# v03b_1.net
KiCad netlist of a schematic drawn in EAGLE
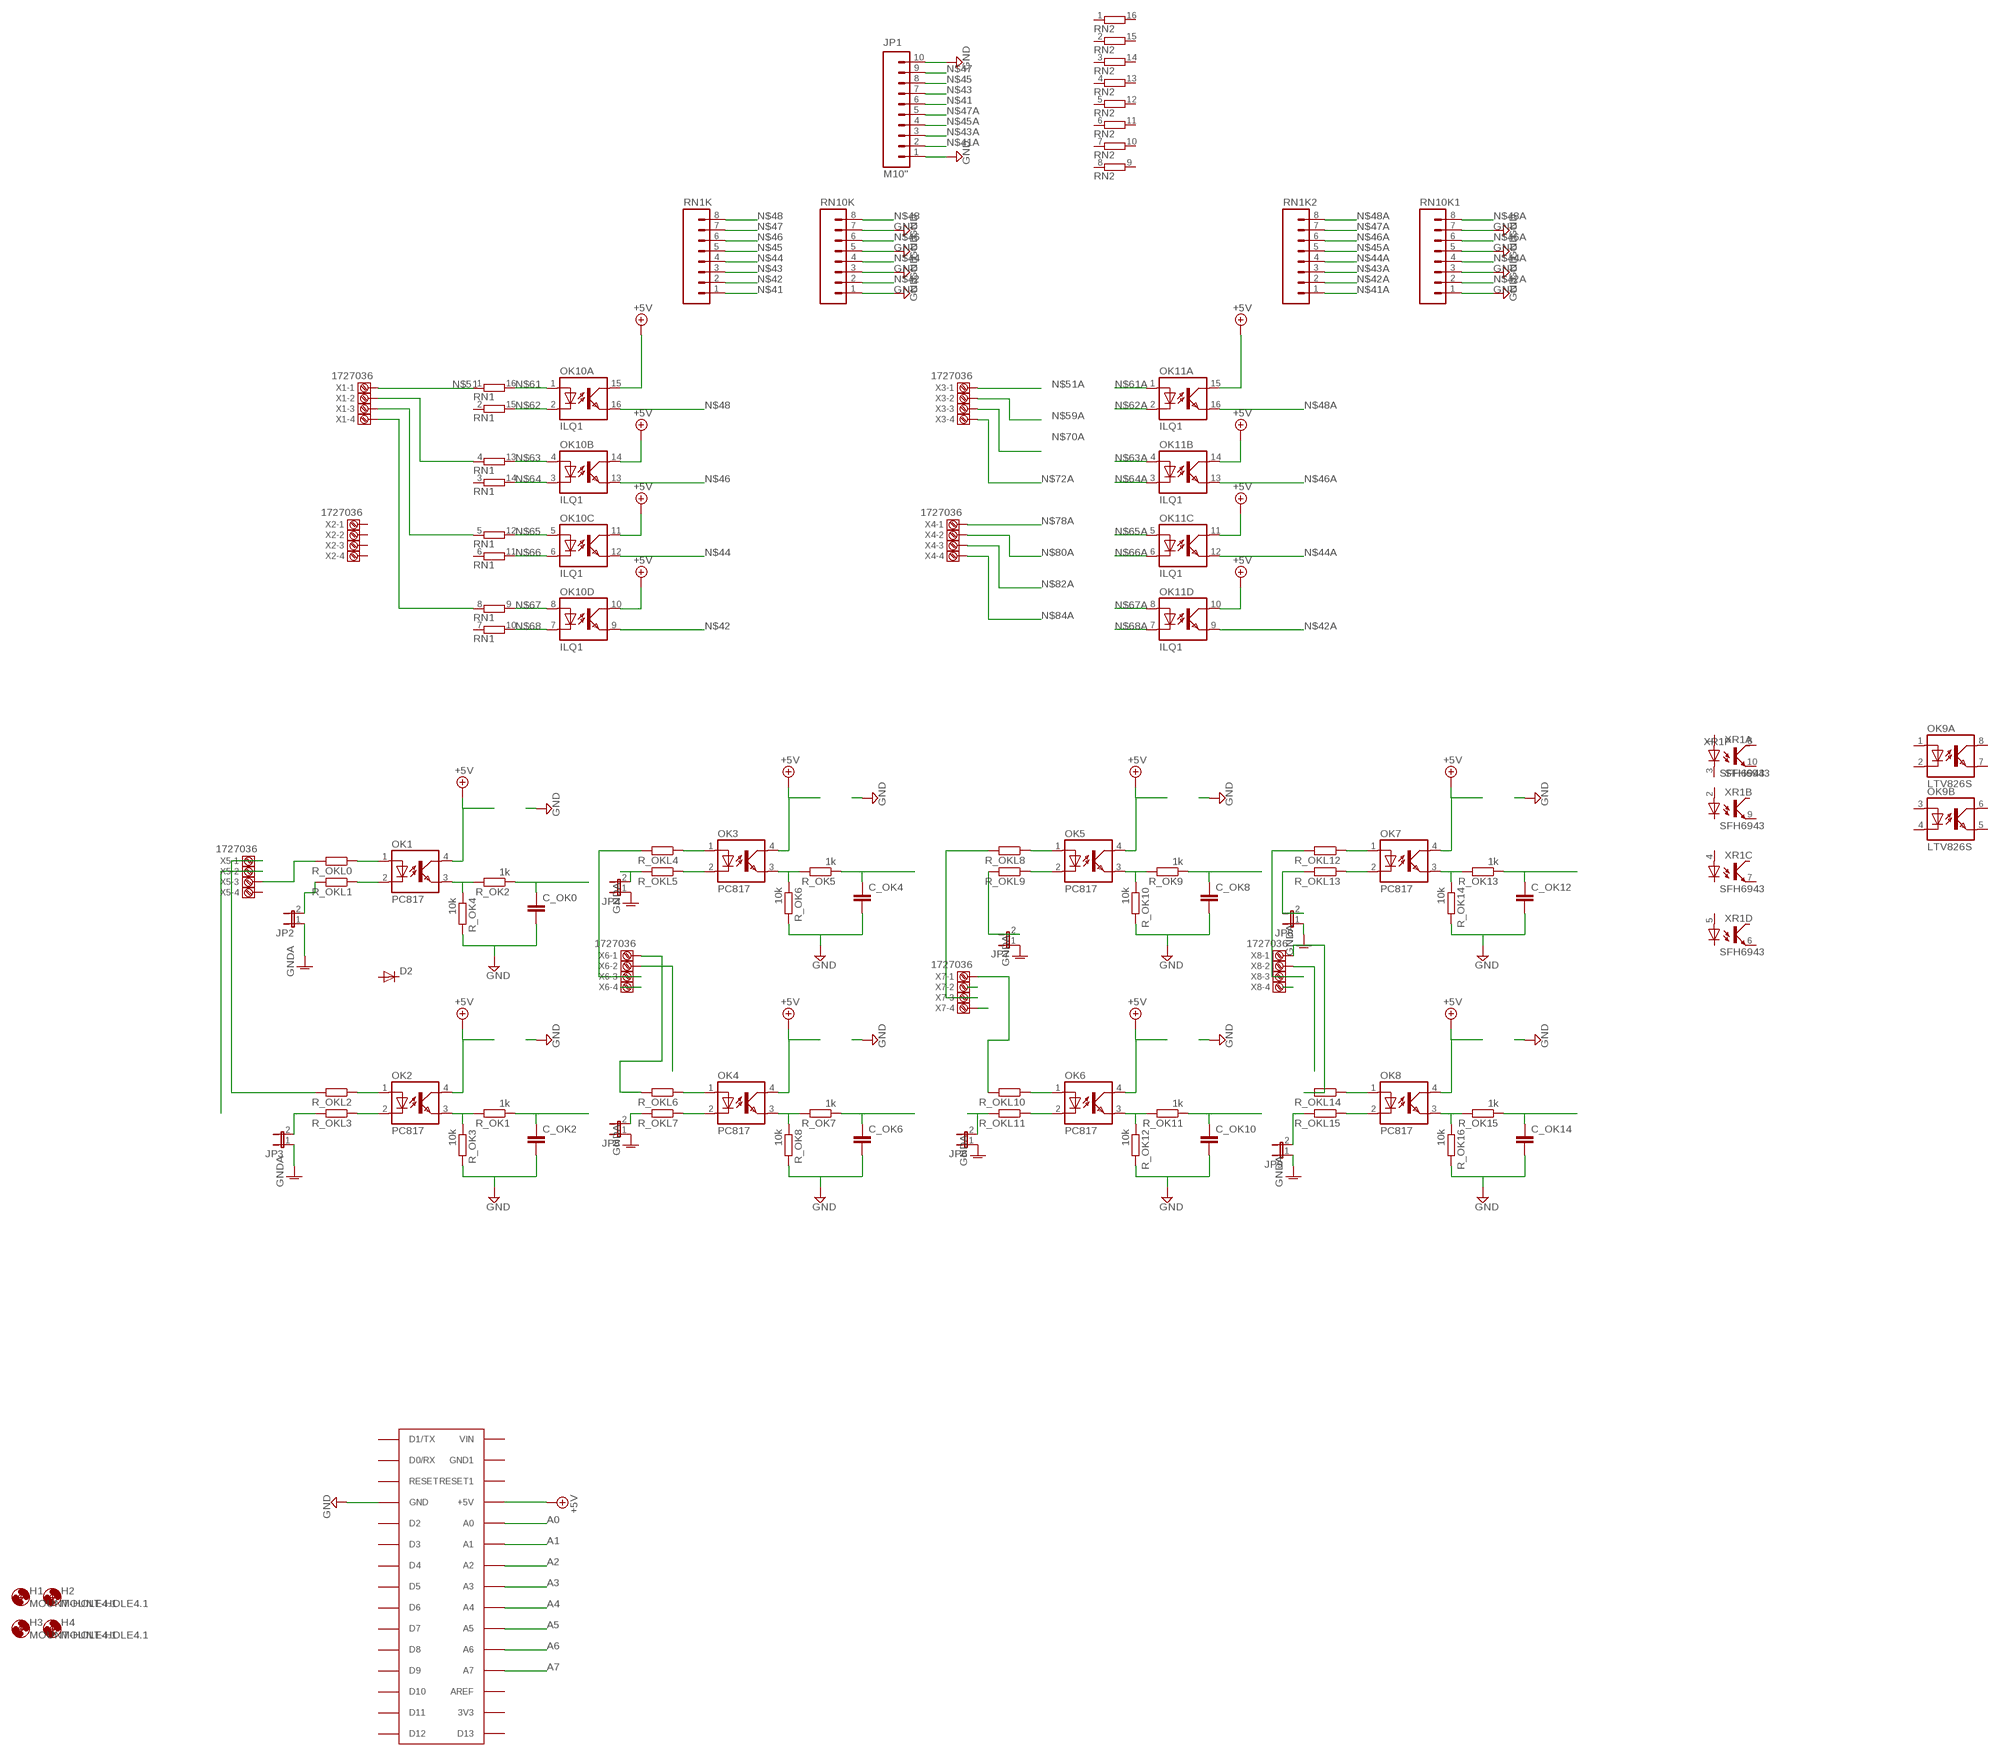
[diagram p0: schematic, sheet 1]

(export (version "E")
  (design (tool "Eeschema 10.0.6"))
  (components
    (comp (ref "C_OK0")
      (value "C-EUC0805")
      (footprint "eagle-import:C0805")
      (libsource (lib "eagle-import") (part "C-EUC0805"))
    )
    (comp (ref "C_OK2")
      (value "C-EUC0805")
      (footprint "eagle-import:C0805")
      (libsource (lib "eagle-import") (part "C-EUC0805"))
    )
    (comp (ref "C_OK4")
      (value "C-EUC0805")
      (footprint "eagle-import:C0805")
      (libsource (lib "eagle-import") (part "C-EUC0805"))
    )
    (comp (ref "C_OK6")
      (value "C-EUC0805")
      (footprint "eagle-import:C0805")
      (libsource (lib "eagle-import") (part "C-EUC0805"))
    )
    (comp (ref "C_OK8")
      (value "C-EUC0805")
      (footprint "eagle-import:C0805")
      (libsource (lib "eagle-import") (part "C-EUC0805"))
    )
    (comp (ref "C_OK10")
      (value "C-EUC0805")
      (footprint "eagle-import:C0805")
      (libsource (lib "eagle-import") (part "C-EUC0805"))
    )
    (comp (ref "C_OK12")
      (value "C-EUC0805")
      (footprint "eagle-import:C0805")
      (libsource (lib "eagle-import") (part "C-EUC0805"))
    )
    (comp (ref "C_OK14")
      (value "C-EUC0805")
      (footprint "eagle-import:C0805")
      (libsource (lib "eagle-import") (part "C-EUC0805"))
    )
    (comp (ref "D2")
      (value "DIODESOD")
      (footprint "eagle-import:SOD-323")
      (libsource (lib "eagle-import") (part "DIODESOD"))
    )
    (comp (ref "H1")
      (value "MOUNT-HOLE4.1")
      (footprint "eagle-import:4,1")
      (libsource (lib "eagle-import") (part "MOUNT-HOLE4.1"))
    )
    (comp (ref "H2")
      (value "MOUNT-HOLE4.1")
      (footprint "eagle-import:4,1")
      (libsource (lib "eagle-import") (part "MOUNT-HOLE4.1"))
    )
    (comp (ref "H3")
      (value "MOUNT-HOLE4.1")
      (footprint "eagle-import:4,1")
      (libsource (lib "eagle-import") (part "MOUNT-HOLE4.1"))
    )
    (comp (ref "H4")
      (value "MOUNT-HOLE4.1")
      (footprint "eagle-import:4,1")
      (libsource (lib "eagle-import") (part "MOUNT-HOLE4.1"))
    )
    (comp (ref "JP1")
      (value "M10\"")
      (footprint "eagle-import:1X10")
      (libsource (lib "eagle-import") (part "M10{dblquote}"))
    )
    (comp (ref "JP2")
      (value "JUMPER-2PTH")
      (footprint "eagle-import:1X02")
      (libsource (lib "eagle-import") (part "JUMPER-2PTH"))
    )
    (comp (ref "JP3")
      (value "JUMPER-2PTH")
      (footprint "eagle-import:1X02")
      (libsource (lib "eagle-import") (part "JUMPER-2PTH"))
    )
    (comp (ref "JP4")
      (value "JUMPER-2PTH")
      (footprint "eagle-import:1X02")
      (libsource (lib "eagle-import") (part "JUMPER-2PTH"))
    )
    (comp (ref "JP5")
      (value "JUMPER-2PTH")
      (footprint "eagle-import:1X02")
      (libsource (lib "eagle-import") (part "JUMPER-2PTH"))
    )
    (comp (ref "JP6")
      (value "JUMPER-2PTH")
      (footprint "eagle-import:1X02")
      (libsource (lib "eagle-import") (part "JUMPER-2PTH"))
    )
    (comp (ref "JP7")
      (value "JUMPER-2PTH")
      (footprint "eagle-import:1X02")
      (libsource (lib "eagle-import") (part "JUMPER-2PTH"))
    )
    (comp (ref "JP8")
      (value "JUMPER-2PTH")
      (footprint "eagle-import:1X02")
      (libsource (lib "eagle-import") (part "JUMPER-2PTH"))
    )
    (comp (ref "JP9")
      (value "JUMPER-2PTH")
      (footprint "eagle-import:1X02")
      (libsource (lib "eagle-import") (part "JUMPER-2PTH"))
    )
    (comp (ref "OK1")
      (value "PC817")
      (footprint "eagle-import:DIL04")
      (fields (field (name "MPN") "PC817X4J000F"))
      (libsource (lib "eagle-import") (part "PC817"))
    )
    (comp (ref "OK2")
      (value "PC817")
      (footprint "eagle-import:DIL04")
      (fields (field (name "MPN") "PC817X4J000F"))
      (libsource (lib "eagle-import") (part "PC817"))
    )
    (comp (ref "OK3")
      (value "PC817")
      (footprint "eagle-import:DIL04")
      (fields (field (name "MPN") "PC817X4J000F"))
      (libsource (lib "eagle-import") (part "PC817"))
    )
    (comp (ref "OK4")
      (value "PC817")
      (footprint "eagle-import:DIL04")
      (fields (field (name "MPN") "PC817X4J000F"))
      (libsource (lib "eagle-import") (part "PC817"))
    )
    (comp (ref "OK5")
      (value "PC817")
      (footprint "eagle-import:DIL04")
      (fields (field (name "MPN") "PC817X4J000F"))
      (libsource (lib "eagle-import") (part "PC817"))
    )
    (comp (ref "OK6")
      (value "PC817")
      (footprint "eagle-import:DIL04")
      (fields (field (name "MPN") "PC817X4J000F"))
      (libsource (lib "eagle-import") (part "PC817"))
    )
    (comp (ref "OK7")
      (value "PC817")
      (footprint "eagle-import:DIL04")
      (fields (field (name "MPN") "PC817X4J000F"))
      (libsource (lib "eagle-import") (part "PC817"))
    )
    (comp (ref "OK8")
      (value "PC817")
      (footprint "eagle-import:DIL04")
      (fields (field (name "MPN") "PC817X4J000F"))
      (libsource (lib "eagle-import") (part "PC817"))
    )
    (comp (ref "OK9")
      (value "LTV826S")
      (footprint "eagle-import:DIL8-SMD")
      (libsource (lib "eagle-import") (part "LTV826S"))
    )
    (comp (ref "OK10")
      (value "ILQ1")
      (footprint "eagle-import:DIL16")
      (fields (field (name "MF") "VISHAY/TELEFUNKEN"))
      (libsource (lib "eagle-import") (part "ILQ1"))
    )
    (comp (ref "OK11")
      (value "ILQ1")
      (footprint "eagle-import:DIL16")
      (fields (field (name "MF") "VISHAY/TELEFUNKEN"))
      (libsource (lib "eagle-import") (part "ILQ1"))
    )
    (comp (ref "RN1")
      (value "8R-PSOMC")
      (footprint "eagle-import:SOMC16")
      (libsource (lib "eagle-import") (part "8R-PSOMC"))
    )
    (comp (ref "RN1K")
      (value "M081X08")
      (footprint "eagle-import:1X08")
      (libsource (lib "eagle-import") (part "M081X08"))
    )
    (comp (ref "RN1K2")
      (value "M081X08")
      (footprint "eagle-import:1X08")
      (libsource (lib "eagle-import") (part "M081X08"))
    )
    (comp (ref "RN2")
      (value "8R-PSOMC")
      (footprint "eagle-import:SOMC16")
      (libsource (lib "eagle-import") (part "8R-PSOMC"))
    )
    (comp (ref "RN10K")
      (value "M081X08")
      (footprint "eagle-import:1X08")
      (libsource (lib "eagle-import") (part "M081X08"))
    )
    (comp (ref "RN10K1")
      (value "M081X08")
      (footprint "eagle-import:1X08")
      (libsource (lib "eagle-import") (part "M081X08"))
    )
    (comp (ref "R_OK1")
      (value "1k")
      (footprint "eagle-import:M0805")
      (libsource (lib "eagle-import") (part "R-EU_M0805"))
    )
    (comp (ref "R_OK2")
      (value "1k")
      (footprint "eagle-import:M0805")
      (libsource (lib "eagle-import") (part "R-EU_M0805"))
    )
    (comp (ref "R_OK3")
      (value "10k")
      (footprint "eagle-import:M0805")
      (libsource (lib "eagle-import") (part "R-EU_M0805"))
    )
    (comp (ref "R_OK4")
      (value "10k")
      (footprint "eagle-import:M0805")
      (libsource (lib "eagle-import") (part "R-EU_M0805"))
    )
    (comp (ref "R_OK5")
      (value "1k")
      (footprint "eagle-import:M0805")
      (libsource (lib "eagle-import") (part "R-EU_M0805"))
    )
    (comp (ref "R_OK6")
      (value "10k")
      (footprint "eagle-import:M0805")
      (libsource (lib "eagle-import") (part "R-EU_M0805"))
    )
    (comp (ref "R_OK7")
      (value "1k")
      (footprint "eagle-import:M0805")
      (libsource (lib "eagle-import") (part "R-EU_M0805"))
    )
    (comp (ref "R_OK8")
      (value "10k")
      (footprint "eagle-import:M0805")
      (libsource (lib "eagle-import") (part "R-EU_M0805"))
    )
    (comp (ref "R_OK9")
      (value "1k")
      (footprint "eagle-import:M0805")
      (libsource (lib "eagle-import") (part "R-EU_M0805"))
    )
    (comp (ref "R_OK10")
      (value "10k")
      (footprint "eagle-import:M0805")
      (libsource (lib "eagle-import") (part "R-EU_M0805"))
    )
    (comp (ref "R_OK11")
      (value "1k")
      (footprint "eagle-import:M0805")
      (libsource (lib "eagle-import") (part "R-EU_M0805"))
    )
    (comp (ref "R_OK12")
      (value "10k")
      (footprint "eagle-import:M0805")
      (libsource (lib "eagle-import") (part "R-EU_M0805"))
    )
    (comp (ref "R_OK13")
      (value "1k")
      (footprint "eagle-import:M0805")
      (libsource (lib "eagle-import") (part "R-EU_M0805"))
    )
    (comp (ref "R_OK14")
      (value "10k")
      (footprint "eagle-import:M0805")
      (libsource (lib "eagle-import") (part "R-EU_M0805"))
    )
    (comp (ref "R_OK15")
      (value "1k")
      (footprint "eagle-import:M0805")
      (libsource (lib "eagle-import") (part "R-EU_M0805"))
    )
    (comp (ref "R_OK16")
      (value "10k")
      (footprint "eagle-import:M0805")
      (libsource (lib "eagle-import") (part "R-EU_M0805"))
    )
    (comp (ref "R_OKL0")
      (value "R-EU_R1210")
      (footprint "eagle-import:R1210")
      (libsource (lib "eagle-import") (part "R-EU_R1210"))
    )
    (comp (ref "R_OKL1")
      (value "R-EU_R1210")
      (footprint "eagle-import:R1210")
      (libsource (lib "eagle-import") (part "R-EU_R1210"))
    )
    (comp (ref "R_OKL2")
      (value "R-EU_R1210")
      (footprint "eagle-import:R1210")
      (libsource (lib "eagle-import") (part "R-EU_R1210"))
    )
    (comp (ref "R_OKL3")
      (value "R-EU_R1210")
      (footprint "eagle-import:R1210")
      (libsource (lib "eagle-import") (part "R-EU_R1210"))
    )
    (comp (ref "R_OKL4")
      (value "R-EU_R1210")
      (footprint "eagle-import:R1210")
      (libsource (lib "eagle-import") (part "R-EU_R1210"))
    )
    (comp (ref "R_OKL5")
      (value "R-EU_R1210")
      (footprint "eagle-import:R1210")
      (libsource (lib "eagle-import") (part "R-EU_R1210"))
    )
    (comp (ref "R_OKL6")
      (value "R-EU_R1210")
      (footprint "eagle-import:R1210")
      (libsource (lib "eagle-import") (part "R-EU_R1210"))
    )
    (comp (ref "R_OKL7")
      (value "R-EU_R1210")
      (footprint "eagle-import:R1210")
      (libsource (lib "eagle-import") (part "R-EU_R1210"))
    )
    (comp (ref "R_OKL8")
      (value "R-EU_R1210")
      (footprint "eagle-import:R1210")
      (libsource (lib "eagle-import") (part "R-EU_R1210"))
    )
    (comp (ref "R_OKL9")
      (value "R-EU_R1210")
      (footprint "eagle-import:R1210")
      (libsource (lib "eagle-import") (part "R-EU_R1210"))
    )
    (comp (ref "R_OKL10")
      (value "R-EU_R1210")
      (footprint "eagle-import:R1210")
      (libsource (lib "eagle-import") (part "R-EU_R1210"))
    )
    (comp (ref "R_OKL11")
      (value "R-EU_R1210")
      (footprint "eagle-import:R1210")
      (libsource (lib "eagle-import") (part "R-EU_R1210"))
    )
    (comp (ref "R_OKL12")
      (value "R-EU_R1210")
      (footprint "eagle-import:R1210")
      (libsource (lib "eagle-import") (part "R-EU_R1210"))
    )
    (comp (ref "R_OKL13")
      (value "R-EU_R1210")
      (footprint "eagle-import:R1210")
      (libsource (lib "eagle-import") (part "R-EU_R1210"))
    )
    (comp (ref "R_OKL14")
      (value "R-EU_R1210")
      (footprint "eagle-import:R1210")
      (libsource (lib "eagle-import") (part "R-EU_R1210"))
    )
    (comp (ref "R_OKL15")
      (value "R-EU_R1210")
      (footprint "eagle-import:R1210")
      (libsource (lib "eagle-import") (part "R-EU_R1210"))
    )
    (comp (ref "U$1")
      (value "ARDUINONANO")
      (footprint "eagle-import:PDIP-32")
      (libsource (lib "eagle-import") (part "ARDUINONANO"))
    )
    (comp (ref "X1")
      (value "1727036")
      (footprint "eagle-import:1727036")
      (fields (field (name "MF") "FARNELL"))
      (libsource (lib "eagle-import") (part "1727036"))
    )
    (comp (ref "X2")
      (value "1727036")
      (footprint "eagle-import:1727036")
      (fields (field (name "MF") "FARNELL"))
      (libsource (lib "eagle-import") (part "1727036"))
    )
    (comp (ref "X3")
      (value "1727036")
      (footprint "eagle-import:1727036")
      (fields (field (name "MF") "FARNELL"))
      (libsource (lib "eagle-import") (part "1727036"))
    )
    (comp (ref "X4")
      (value "1727036")
      (footprint "eagle-import:1727036")
      (fields (field (name "MF") "FARNELL"))
      (libsource (lib "eagle-import") (part "1727036"))
    )
    (comp (ref "X5")
      (value "1727036")
      (footprint "eagle-import:1727036")
      (fields (field (name "MF") "FARNELL"))
      (libsource (lib "eagle-import") (part "1727036"))
    )
    (comp (ref "X6")
      (value "1727036")
      (footprint "eagle-import:1727036")
      (fields (field (name "MF") "FARNELL"))
      (libsource (lib "eagle-import") (part "1727036"))
    )
    (comp (ref "X7")
      (value "1727036")
      (footprint "eagle-import:1727036")
      (fields (field (name "MF") "FARNELL"))
      (libsource (lib "eagle-import") (part "1727036"))
    )
    (comp (ref "X8")
      (value "1727036")
      (footprint "eagle-import:1727036")
      (fields (field (name "MF") "FARNELL"))
      (libsource (lib "eagle-import") (part "1727036"))
    )
    (comp (ref "XR1")
      (value "SFH6943")
      (footprint "eagle-import:SOT223_10")
      (fields (field (name "MPN") "SFH6943A-4T"))
      (libsource (lib "eagle-import") (part "SFH6943"))
    )
  )
  (nets
    (net (code "1") (name "+5V") (class "Default")
      (node (ref "OK1") (pin "4") (pinfunction "COL_4") (pintype "passive"))
      (node (ref "OK10") (pin "10") (pinfunction "COL_10") (pintype "passive"))
      (node (ref "OK10") (pin "11") (pinfunction "COL_11") (pintype "passive"))
      (node (ref "OK10") (pin "14") (pinfunction "COL_14") (pintype "passive"))
      (node (ref "OK10") (pin "15") (pinfunction "COL_15") (pintype "passive"))
      (node (ref "OK11") (pin "10") (pinfunction "COL_10") (pintype "passive"))
      (node (ref "OK11") (pin "11") (pinfunction "COL_11") (pintype "passive"))
      (node (ref "OK11") (pin "14") (pinfunction "COL_14") (pintype "passive"))
      (node (ref "OK11") (pin "15") (pinfunction "COL_15") (pintype "passive"))
      (node (ref "OK2") (pin "4") (pinfunction "COL_4") (pintype "passive"))
      (node (ref "OK3") (pin "4") (pinfunction "COL_4") (pintype "passive"))
      (node (ref "OK4") (pin "4") (pinfunction "COL_4") (pintype "passive"))
      (node (ref "OK5") (pin "4") (pinfunction "COL_4") (pintype "passive"))
      (node (ref "OK6") (pin "4") (pinfunction "COL_4") (pintype "passive"))
      (node (ref "OK7") (pin "4") (pinfunction "COL_4") (pintype "passive"))
      (node (ref "OK8") (pin "4") (pinfunction "COL_4") (pintype "passive"))
      (node (ref "U$1") (pin "+5V") (pinfunction "+5V_+5V") (pintype "bidirectional"))
    )
    (net (code "2") (name "/A0") (class "Default")
      (node (ref "C_OK0") (pin "1") (pinfunction "1_1") (pintype "passive"))
      (node (ref "R_OK2") (pin "1") (pinfunction "1_1") (pintype "passive"))
      (node (ref "U$1") (pin "A0") (pinfunction "A0_A0") (pintype "bidirectional"))
    )
    (net (code "3") (name "/A1") (class "Default")
      (node (ref "C_OK2") (pin "1") (pinfunction "1_1") (pintype "passive"))
      (node (ref "R_OK1") (pin "1") (pinfunction "1_1") (pintype "passive"))
      (node (ref "U$1") (pin "A1") (pinfunction "A1_A1") (pintype "bidirectional"))
    )
    (net (code "4") (name "/A2") (class "Default")
      (node (ref "C_OK4") (pin "1") (pinfunction "1_1") (pintype "passive"))
      (node (ref "R_OK5") (pin "1") (pinfunction "1_1") (pintype "passive"))
      (node (ref "U$1") (pin "A2") (pinfunction "A2_A2") (pintype "bidirectional"))
    )
    (net (code "5") (name "/A3") (class "Default")
      (node (ref "C_OK6") (pin "1") (pinfunction "1_1") (pintype "passive"))
      (node (ref "R_OK7") (pin "1") (pinfunction "1_1") (pintype "passive"))
      (node (ref "U$1") (pin "A3") (pinfunction "A3_A3") (pintype "bidirectional"))
    )
    (net (code "6") (name "/A4") (class "Default")
      (node (ref "C_OK8") (pin "1") (pinfunction "1_1") (pintype "passive"))
      (node (ref "R_OK9") (pin "1") (pinfunction "1_1") (pintype "passive"))
      (node (ref "U$1") (pin "A4") (pinfunction "A4_A4") (pintype "bidirectional"))
    )
    (net (code "7") (name "/A5") (class "Default")
      (node (ref "C_OK10") (pin "1") (pinfunction "1_1") (pintype "passive"))
      (node (ref "R_OK11") (pin "1") (pinfunction "1_1") (pintype "passive"))
      (node (ref "U$1") (pin "A5") (pinfunction "A5_A5") (pintype "bidirectional"))
    )
    (net (code "8") (name "/A6") (class "Default")
      (node (ref "C_OK12") (pin "1") (pinfunction "1_1") (pintype "passive"))
      (node (ref "R_OK13") (pin "1") (pinfunction "1_1") (pintype "passive"))
      (node (ref "U$1") (pin "A6") (pinfunction "A6_A6") (pintype "bidirectional"))
    )
    (net (code "9") (name "/A7") (class "Default")
      (node (ref "C_OK14") (pin "1") (pinfunction "1_1") (pintype "passive"))
      (node (ref "R_OK15") (pin "1") (pinfunction "1_1") (pintype "passive"))
      (node (ref "U$1") (pin "A7") (pinfunction "A7_A7") (pintype "bidirectional"))
    )
    (net (code "10") (name "/N$41") (class "Default")
      (node (ref "JP1") (pin "6") (pinfunction "6_6") (pintype "passive"))
      (node (ref "RN1K") (pin "1") (pinfunction "1_1") (pintype "passive"))
    )
    (net (code "11") (name "/N$41A") (class "Default")
      (node (ref "JP1") (pin "2") (pinfunction "2_2") (pintype "passive"))
      (node (ref "RN1K2") (pin "1") (pinfunction "1_1") (pintype "passive"))
    )
    (net (code "12") (name "/N$42") (class "Default")
      (node (ref "OK10") (pin "9") (pinfunction "EMIT_9") (pintype "passive"))
      (node (ref "RN10K") (pin "2") (pinfunction "2_2") (pintype "passive"))
      (node (ref "RN1K") (pin "2") (pinfunction "2_2") (pintype "passive"))
    )
    (net (code "13") (name "/N$42A") (class "Default")
      (node (ref "OK11") (pin "9") (pinfunction "EMIT_9") (pintype "passive"))
      (node (ref "RN10K1") (pin "2") (pinfunction "2_2") (pintype "passive"))
      (node (ref "RN1K2") (pin "2") (pinfunction "2_2") (pintype "passive"))
    )
    (net (code "14") (name "/N$43") (class "Default")
      (node (ref "JP1") (pin "7") (pinfunction "7_7") (pintype "passive"))
      (node (ref "RN1K") (pin "3") (pinfunction "3_3") (pintype "passive"))
    )
    (net (code "15") (name "/N$43A") (class "Default")
      (node (ref "JP1") (pin "3") (pinfunction "3_3") (pintype "passive"))
      (node (ref "RN1K2") (pin "3") (pinfunction "3_3") (pintype "passive"))
    )
    (net (code "16") (name "/N$44") (class "Default")
      (node (ref "OK10") (pin "12") (pinfunction "EMIT_12") (pintype "passive"))
      (node (ref "RN10K") (pin "4") (pinfunction "4_4") (pintype "passive"))
      (node (ref "RN1K") (pin "4") (pinfunction "4_4") (pintype "passive"))
    )
    (net (code "17") (name "/N$44A") (class "Default")
      (node (ref "OK11") (pin "12") (pinfunction "EMIT_12") (pintype "passive"))
      (node (ref "RN10K1") (pin "4") (pinfunction "4_4") (pintype "passive"))
      (node (ref "RN1K2") (pin "4") (pinfunction "4_4") (pintype "passive"))
    )
    (net (code "18") (name "/N$45") (class "Default")
      (node (ref "JP1") (pin "8") (pinfunction "8_8") (pintype "passive"))
      (node (ref "RN1K") (pin "5") (pinfunction "5_5") (pintype "passive"))
    )
    (net (code "19") (name "/N$45A") (class "Default")
      (node (ref "JP1") (pin "4") (pinfunction "4_4") (pintype "passive"))
      (node (ref "RN1K2") (pin "5") (pinfunction "5_5") (pintype "passive"))
    )
    (net (code "20") (name "/N$46") (class "Default")
      (node (ref "OK10") (pin "13") (pinfunction "EMIT_13") (pintype "passive"))
      (node (ref "RN10K") (pin "6") (pinfunction "6_6") (pintype "passive"))
      (node (ref "RN1K") (pin "6") (pinfunction "6_6") (pintype "passive"))
    )
    (net (code "21") (name "/N$46A") (class "Default")
      (node (ref "OK11") (pin "13") (pinfunction "EMIT_13") (pintype "passive"))
      (node (ref "RN10K1") (pin "6") (pinfunction "6_6") (pintype "passive"))
      (node (ref "RN1K2") (pin "6") (pinfunction "6_6") (pintype "passive"))
    )
    (net (code "22") (name "/N$47") (class "Default")
      (node (ref "JP1") (pin "9") (pinfunction "9_9") (pintype "passive"))
      (node (ref "RN1K") (pin "7") (pinfunction "7_7") (pintype "passive"))
    )
    (net (code "23") (name "/N$47A") (class "Default")
      (node (ref "JP1") (pin "5") (pinfunction "5_5") (pintype "passive"))
      (node (ref "RN1K2") (pin "7") (pinfunction "7_7") (pintype "passive"))
    )
    (net (code "24") (name "/N$48") (class "Default")
      (node (ref "OK10") (pin "16") (pinfunction "EMIT_16") (pintype "passive"))
      (node (ref "RN10K") (pin "8") (pinfunction "8_8") (pintype "passive"))
      (node (ref "RN1K") (pin "8") (pinfunction "8_8") (pintype "passive"))
    )
    (net (code "25") (name "/N$48A") (class "Default")
      (node (ref "OK11") (pin "16") (pinfunction "EMIT_16") (pintype "passive"))
      (node (ref "RN10K1") (pin "8") (pinfunction "8_8") (pintype "passive"))
      (node (ref "RN1K2") (pin "8") (pinfunction "8_8") (pintype "passive"))
    )
    (net (code "26") (name "/N$51") (class "Default")
      (node (ref "RN1") (pin "1") (pinfunction "1_1") (pintype "passive"))
      (node (ref "X1") (pin "1") (pinfunction "1_1") (pintype "passive"))
    )
    (net (code "27") (name "/N$51A") (class "Default")
      (node (ref "X3") (pin "1") (pinfunction "1_1") (pintype "passive"))
    )
    (net (code "28") (name "/N$59A") (class "Default")
      (node (ref "X3") (pin "2") (pinfunction "1_2") (pintype "passive"))
    )
    (net (code "29") (name "/N$61") (class "Default")
      (node (ref "OK10") (pin "1") (pinfunction "A_1") (pintype "passive"))
      (node (ref "RN1") (pin "16") (pinfunction "2_16") (pintype "passive"))
    )
    (net (code "30") (name "/N$61A") (class "Default")
      (node (ref "OK11") (pin "1") (pinfunction "A_1") (pintype "passive"))
    )
    (net (code "31") (name "/N$62") (class "Default")
      (node (ref "OK10") (pin "2") (pinfunction "C_2") (pintype "passive"))
      (node (ref "RN1") (pin "15") (pinfunction "2_15") (pintype "passive"))
    )
    (net (code "32") (name "/N$62A") (class "Default")
      (node (ref "OK11") (pin "2") (pinfunction "C_2") (pintype "passive"))
    )
    (net (code "33") (name "/N$63") (class "Default")
      (node (ref "OK10") (pin "4") (pinfunction "A_4") (pintype "passive"))
      (node (ref "RN1") (pin "13") (pinfunction "2_13") (pintype "passive"))
    )
    (net (code "34") (name "/N$63A") (class "Default")
      (node (ref "OK11") (pin "4") (pinfunction "A_4") (pintype "passive"))
    )
    (net (code "35") (name "/N$64") (class "Default")
      (node (ref "OK10") (pin "3") (pinfunction "C_3") (pintype "passive"))
      (node (ref "RN1") (pin "14") (pinfunction "2_14") (pintype "passive"))
    )
    (net (code "36") (name "/N$64A") (class "Default")
      (node (ref "OK11") (pin "3") (pinfunction "C_3") (pintype "passive"))
    )
    (net (code "37") (name "/N$65") (class "Default")
      (node (ref "OK10") (pin "5") (pinfunction "A_5") (pintype "passive"))
      (node (ref "RN1") (pin "12") (pinfunction "2_12") (pintype "passive"))
    )
    (net (code "38") (name "/N$65A") (class "Default")
      (node (ref "OK11") (pin "5") (pinfunction "A_5") (pintype "passive"))
    )
    (net (code "39") (name "/N$66") (class "Default")
      (node (ref "OK10") (pin "6") (pinfunction "C_6") (pintype "passive"))
      (node (ref "RN1") (pin "11") (pinfunction "2_11") (pintype "passive"))
    )
    (net (code "40") (name "/N$66A") (class "Default")
      (node (ref "OK11") (pin "6") (pinfunction "C_6") (pintype "passive"))
    )
    (net (code "41") (name "/N$67") (class "Default")
      (node (ref "OK10") (pin "8") (pinfunction "A_8") (pintype "passive"))
      (node (ref "RN1") (pin "9") (pinfunction "2_9") (pintype "passive"))
    )
    (net (code "42") (name "/N$67A") (class "Default")
      (node (ref "OK11") (pin "8") (pinfunction "A_8") (pintype "passive"))
    )
    (net (code "43") (name "/N$68") (class "Default")
      (node (ref "OK10") (pin "7") (pinfunction "C_7") (pintype "passive"))
      (node (ref "RN1") (pin "10") (pinfunction "2_10") (pintype "passive"))
    )
    (net (code "44") (name "/N$68A") (class "Default")
      (node (ref "OK11") (pin "7") (pinfunction "C_7") (pintype "passive"))
    )
    (net (code "45") (name "/N$70A") (class "Default")
      (node (ref "X3") (pin "3") (pinfunction "1_3") (pintype "passive"))
    )
    (net (code "46") (name "/N$72A") (class "Default")
      (node (ref "X3") (pin "4") (pinfunction "1_4") (pintype "passive"))
    )
    (net (code "47") (name "/N$78A") (class "Default")
      (node (ref "X4") (pin "1") (pinfunction "1_1") (pintype "passive"))
    )
    (net (code "48") (name "/N$80A") (class "Default")
      (node (ref "X4") (pin "2") (pinfunction "1_2") (pintype "passive"))
    )
    (net (code "49") (name "/N$82A") (class "Default")
      (node (ref "X4") (pin "3") (pinfunction "1_3") (pintype "passive"))
    )
    (net (code "50") (name "/N$84A") (class "Default")
      (node (ref "X4") (pin "4") (pinfunction "1_4") (pintype "passive"))
    )
    (net (code "51") (name "GND") (class "Default")
      (node (ref "C_OK0") (pin "2") (pinfunction "2_2") (pintype "passive"))
      (node (ref "C_OK10") (pin "2") (pinfunction "2_2") (pintype "passive"))
      (node (ref "C_OK12") (pin "2") (pinfunction "2_2") (pintype "passive"))
      (node (ref "C_OK14") (pin "2") (pinfunction "2_2") (pintype "passive"))
      (node (ref "C_OK2") (pin "2") (pinfunction "2_2") (pintype "passive"))
      (node (ref "C_OK4") (pin "2") (pinfunction "2_2") (pintype "passive"))
      (node (ref "C_OK6") (pin "2") (pinfunction "2_2") (pintype "passive"))
      (node (ref "C_OK8") (pin "2") (pinfunction "2_2") (pintype "passive"))
      (node (ref "JP1") (pin "1") (pinfunction "1_1") (pintype "passive"))
      (node (ref "JP1") (pin "10") (pinfunction "10_10") (pintype "passive"))
      (node (ref "RN10K") (pin "1") (pinfunction "1_1") (pintype "passive"))
      (node (ref "RN10K") (pin "3") (pinfunction "3_3") (pintype "passive"))
      (node (ref "RN10K") (pin "5") (pinfunction "5_5") (pintype "passive"))
      (node (ref "RN10K") (pin "7") (pinfunction "7_7") (pintype "passive"))
      (node (ref "RN10K1") (pin "1") (pinfunction "1_1") (pintype "passive"))
      (node (ref "RN10K1") (pin "3") (pinfunction "3_3") (pintype "passive"))
      (node (ref "RN10K1") (pin "5") (pinfunction "5_5") (pintype "passive"))
      (node (ref "RN10K1") (pin "7") (pinfunction "7_7") (pintype "passive"))
      (node (ref "R_OK10") (pin "2") (pinfunction "2_2") (pintype "passive"))
      (node (ref "R_OK12") (pin "2") (pinfunction "2_2") (pintype "passive"))
      (node (ref "R_OK14") (pin "2") (pinfunction "2_2") (pintype "passive"))
      (node (ref "R_OK16") (pin "2") (pinfunction "2_2") (pintype "passive"))
      (node (ref "R_OK3") (pin "2") (pinfunction "2_2") (pintype "passive"))
      (node (ref "R_OK4") (pin "2") (pinfunction "2_2") (pintype "passive"))
      (node (ref "R_OK6") (pin "2") (pinfunction "2_2") (pintype "passive"))
      (node (ref "R_OK8") (pin "2") (pinfunction "2_2") (pintype "passive"))
      (node (ref "U$1") (pin "GND") (pinfunction "GND_GND") (pintype "bidirectional"))
    )
    (net (code "52") (name "GNDA") (class "Default")
      (node (ref "JP2") (pin "1") (pinfunction "1_1") (pintype "passive"))
      (node (ref "JP3") (pin "1") (pinfunction "1_1") (pintype "passive"))
      (node (ref "JP4") (pin "1") (pinfunction "1_1") (pintype "passive"))
      (node (ref "JP5") (pin "1") (pinfunction "1_1") (pintype "passive"))
      (node (ref "JP6") (pin "1") (pinfunction "1_1") (pintype "passive"))
      (node (ref "JP7") (pin "1") (pinfunction "1_1") (pintype "passive"))
      (node (ref "JP8") (pin "1") (pinfunction "1_1") (pintype "passive"))
      (node (ref "JP9") (pin "1") (pinfunction "1_1") (pintype "passive"))
    )
    (net (code "53") (name "Net-(JP2-Pad2)") (class "Default")
      (node (ref "JP2") (pin "2") (pinfunction "2_2") (pintype "passive"))
      (node (ref "R_OKL1") (pin "2") (pinfunction "2_2") (pintype "passive"))
    )
    (net (code "54") (name "Net-(JP3-Pad2)") (class "Default")
      (node (ref "JP3") (pin "2") (pinfunction "2_2") (pintype "passive"))
      (node (ref "R_OKL3") (pin "2") (pinfunction "2_2") (pintype "passive"))
    )
    (net (code "55") (name "Net-(JP4-Pad2)") (class "Default")
      (node (ref "JP4") (pin "2") (pinfunction "2_2") (pintype "passive"))
      (node (ref "R_OKL5") (pin "2") (pinfunction "2_2") (pintype "passive"))
    )
    (net (code "56") (name "Net-(JP5-Pad2)") (class "Default")
      (node (ref "JP5") (pin "2") (pinfunction "2_2") (pintype "passive"))
      (node (ref "R_OKL7") (pin "2") (pinfunction "2_2") (pintype "passive"))
    )
    (net (code "57") (name "Net-(JP6-Pad2)") (class "Default")
      (node (ref "JP6") (pin "2") (pinfunction "2_2") (pintype "passive"))
      (node (ref "R_OKL11") (pin "2") (pinfunction "2_2") (pintype "passive"))
    )
    (net (code "58") (name "Net-(JP7-Pad2)") (class "Default")
      (node (ref "JP7") (pin "2") (pinfunction "2_2") (pintype "passive"))
      (node (ref "R_OKL9") (pin "2") (pinfunction "2_2") (pintype "passive"))
    )
    (net (code "59") (name "Net-(JP8-Pad2)") (class "Default")
      (node (ref "JP8") (pin "2") (pinfunction "2_2") (pintype "passive"))
      (node (ref "R_OKL13") (pin "2") (pinfunction "2_2") (pintype "passive"))
    )
    (net (code "60") (name "Net-(JP9-Pad2)") (class "Default")
      (node (ref "JP9") (pin "2") (pinfunction "2_2") (pintype "passive"))
      (node (ref "R_OKL15") (pin "2") (pinfunction "2_2") (pintype "passive"))
    )
    (net (code "61") (name "Net-(OK1-A)") (class "Default")
      (node (ref "OK1") (pin "1") (pinfunction "A_1") (pintype "passive"))
      (node (ref "R_OKL0") (pin "1") (pinfunction "1_1") (pintype "passive"))
    )
    (net (code "62") (name "Net-(OK1-C)") (class "Default")
      (node (ref "OK1") (pin "2") (pinfunction "C_2") (pintype "passive"))
      (node (ref "R_OKL1") (pin "1") (pinfunction "1_1") (pintype "passive"))
    )
    (net (code "63") (name "Net-(OK1-EMIT)") (class "Default")
      (node (ref "OK1") (pin "3") (pinfunction "EMIT_3") (pintype "passive"))
      (node (ref "R_OK2") (pin "2") (pinfunction "2_2") (pintype "passive"))
      (node (ref "R_OK4") (pin "1") (pinfunction "1_1") (pintype "passive"))
    )
    (net (code "64") (name "Net-(OK2-A)") (class "Default")
      (node (ref "OK2") (pin "1") (pinfunction "A_1") (pintype "passive"))
      (node (ref "R_OKL2") (pin "1") (pinfunction "1_1") (pintype "passive"))
    )
    (net (code "65") (name "Net-(OK2-C)") (class "Default")
      (node (ref "OK2") (pin "2") (pinfunction "C_2") (pintype "passive"))
      (node (ref "R_OKL3") (pin "1") (pinfunction "1_1") (pintype "passive"))
    )
    (net (code "66") (name "Net-(OK2-EMIT)") (class "Default")
      (node (ref "OK2") (pin "3") (pinfunction "EMIT_3") (pintype "passive"))
      (node (ref "R_OK1") (pin "2") (pinfunction "2_2") (pintype "passive"))
      (node (ref "R_OK3") (pin "1") (pinfunction "1_1") (pintype "passive"))
    )
    (net (code "67") (name "Net-(OK3-A)") (class "Default")
      (node (ref "OK3") (pin "1") (pinfunction "A_1") (pintype "passive"))
      (node (ref "R_OKL4") (pin "1") (pinfunction "1_1") (pintype "passive"))
    )
    (net (code "68") (name "Net-(OK3-C)") (class "Default")
      (node (ref "OK3") (pin "2") (pinfunction "C_2") (pintype "passive"))
      (node (ref "R_OKL5") (pin "1") (pinfunction "1_1") (pintype "passive"))
    )
    (net (code "69") (name "Net-(OK3-EMIT)") (class "Default")
      (node (ref "OK3") (pin "3") (pinfunction "EMIT_3") (pintype "passive"))
      (node (ref "R_OK5") (pin "2") (pinfunction "2_2") (pintype "passive"))
      (node (ref "R_OK6") (pin "1") (pinfunction "1_1") (pintype "passive"))
    )
    (net (code "70") (name "Net-(OK4-A)") (class "Default")
      (node (ref "OK4") (pin "1") (pinfunction "A_1") (pintype "passive"))
      (node (ref "R_OKL6") (pin "1") (pinfunction "1_1") (pintype "passive"))
    )
    (net (code "71") (name "Net-(OK4-C)") (class "Default")
      (node (ref "OK4") (pin "2") (pinfunction "C_2") (pintype "passive"))
      (node (ref "R_OKL7") (pin "1") (pinfunction "1_1") (pintype "passive"))
    )
    (net (code "72") (name "Net-(OK4-EMIT)") (class "Default")
      (node (ref "OK4") (pin "3") (pinfunction "EMIT_3") (pintype "passive"))
      (node (ref "R_OK7") (pin "2") (pinfunction "2_2") (pintype "passive"))
      (node (ref "R_OK8") (pin "1") (pinfunction "1_1") (pintype "passive"))
    )
    (net (code "73") (name "Net-(OK5-A)") (class "Default")
      (node (ref "OK5") (pin "1") (pinfunction "A_1") (pintype "passive"))
      (node (ref "R_OKL8") (pin "1") (pinfunction "1_1") (pintype "passive"))
    )
    (net (code "74") (name "Net-(OK5-C)") (class "Default")
      (node (ref "OK5") (pin "2") (pinfunction "C_2") (pintype "passive"))
      (node (ref "R_OKL9") (pin "1") (pinfunction "1_1") (pintype "passive"))
    )
    (net (code "75") (name "Net-(OK5-EMIT)") (class "Default")
      (node (ref "OK5") (pin "3") (pinfunction "EMIT_3") (pintype "passive"))
      (node (ref "R_OK10") (pin "1") (pinfunction "1_1") (pintype "passive"))
      (node (ref "R_OK9") (pin "2") (pinfunction "2_2") (pintype "passive"))
    )
    (net (code "76") (name "Net-(OK6-A)") (class "Default")
      (node (ref "OK6") (pin "1") (pinfunction "A_1") (pintype "passive"))
      (node (ref "R_OKL10") (pin "1") (pinfunction "1_1") (pintype "passive"))
    )
    (net (code "77") (name "Net-(OK6-C)") (class "Default")
      (node (ref "OK6") (pin "2") (pinfunction "C_2") (pintype "passive"))
      (node (ref "R_OKL11") (pin "1") (pinfunction "1_1") (pintype "passive"))
    )
    (net (code "78") (name "Net-(OK6-EMIT)") (class "Default")
      (node (ref "OK6") (pin "3") (pinfunction "EMIT_3") (pintype "passive"))
      (node (ref "R_OK11") (pin "2") (pinfunction "2_2") (pintype "passive"))
      (node (ref "R_OK12") (pin "1") (pinfunction "1_1") (pintype "passive"))
    )
    (net (code "79") (name "Net-(OK7-A)") (class "Default")
      (node (ref "OK7") (pin "1") (pinfunction "A_1") (pintype "passive"))
      (node (ref "R_OKL12") (pin "1") (pinfunction "1_1") (pintype "passive"))
    )
    (net (code "80") (name "Net-(OK7-C)") (class "Default")
      (node (ref "OK7") (pin "2") (pinfunction "C_2") (pintype "passive"))
      (node (ref "R_OKL13") (pin "1") (pinfunction "1_1") (pintype "passive"))
    )
    (net (code "81") (name "Net-(OK7-EMIT)") (class "Default")
      (node (ref "OK7") (pin "3") (pinfunction "EMIT_3") (pintype "passive"))
      (node (ref "R_OK13") (pin "2") (pinfunction "2_2") (pintype "passive"))
      (node (ref "R_OK14") (pin "1") (pinfunction "1_1") (pintype "passive"))
    )
    (net (code "82") (name "Net-(OK8-A)") (class "Default")
      (node (ref "OK8") (pin "1") (pinfunction "A_1") (pintype "passive"))
      (node (ref "R_OKL14") (pin "1") (pinfunction "1_1") (pintype "passive"))
    )
    (net (code "83") (name "Net-(OK8-C)") (class "Default")
      (node (ref "OK8") (pin "2") (pinfunction "C_2") (pintype "passive"))
      (node (ref "R_OKL15") (pin "1") (pinfunction "1_1") (pintype "passive"))
    )
    (net (code "84") (name "Net-(OK8-EMIT)") (class "Default")
      (node (ref "OK8") (pin "3") (pinfunction "EMIT_3") (pintype "passive"))
      (node (ref "R_OK15") (pin "2") (pinfunction "2_2") (pintype "passive"))
      (node (ref "R_OK16") (pin "1") (pinfunction "1_1") (pintype "passive"))
    )
    (net (code "85") (name "Net-(RN1D-1)") (class "Default")
      (node (ref "RN1") (pin "4") (pinfunction "1_4") (pintype "passive"))
      (node (ref "X1") (pin "2") (pinfunction "1_2") (pintype "passive"))
    )
    (net (code "86") (name "Net-(RN1E-1)") (class "Default")
      (node (ref "RN1") (pin "5") (pinfunction "1_5") (pintype "passive"))
      (node (ref "X1") (pin "3") (pinfunction "1_3") (pintype "passive"))
    )
    (net (code "87") (name "Net-(RN1H-1)") (class "Default")
      (node (ref "RN1") (pin "8") (pinfunction "1_8") (pintype "passive"))
      (node (ref "X1") (pin "4") (pinfunction "1_4") (pintype "passive"))
    )
    (net (code "88") (name "Net-(R_OKL2-Pad2)") (class "Default")
      (node (ref "R_OKL2") (pin "2") (pinfunction "2_2") (pintype "passive"))
      (node (ref "X5") (pin "1") (pinfunction "1_1") (pintype "passive"))
    )
    (net (code "89") (name "Net-(R_OKL6-Pad2)") (class "Default")
      (node (ref "R_OKL6") (pin "2") (pinfunction "2_2") (pintype "passive"))
      (node (ref "X6") (pin "1") (pinfunction "1_1") (pintype "passive"))
    )
    (net (code "90") (name "Net-(R_OKL10-Pad2)") (class "Default")
      (node (ref "R_OKL10") (pin "2") (pinfunction "2_2") (pintype "passive"))
      (node (ref "X7") (pin "1") (pinfunction "1_1") (pintype "passive"))
    )
    (net (code "91") (name "Net-(R_OKL14-Pad2)") (class "Default")
      (node (ref "R_OKL14") (pin "2") (pinfunction "2_2") (pintype "passive"))
      (node (ref "X8") (pin "1") (pinfunction "1_1") (pintype "passive"))
    )
    (net (code "92") (name "Net-(X5C-1)") (class "Default")
      (node (ref "R_OKL0") (pin "2") (pinfunction "2_2") (pintype "passive"))
      (node (ref "X5") (pin "3") (pinfunction "1_3") (pintype "passive"))
    )
    (net (code "93") (name "Net-(X6C-1)") (class "Default")
      (node (ref "R_OKL4") (pin "2") (pinfunction "2_2") (pintype "passive"))
      (node (ref "X6") (pin "3") (pinfunction "1_3") (pintype "passive"))
    )
    (net (code "94") (name "Net-(X7C-1)") (class "Default")
      (node (ref "R_OKL8") (pin "2") (pinfunction "2_2") (pintype "passive"))
      (node (ref "X7") (pin "3") (pinfunction "1_3") (pintype "passive"))
    )
    (net (code "95") (name "Net-(X8C-1)") (class "Default")
      (node (ref "R_OKL12") (pin "2") (pinfunction "2_2") (pintype "passive"))
      (node (ref "X8") (pin "3") (pinfunction "1_3") (pintype "passive"))
    )
    (net (code "96") (name "unconnected-(D2-A-Pad2)") (class "Default")
      (node (ref "D2") (pin "2") (pinfunction "A_2") (pintype "passive"))
    )
    (net (code "97") (name "unconnected-(D2-C-Pad1)") (class "Default")
      (node (ref "D2") (pin "1") (pinfunction "C_1") (pintype "passive"))
    )
    (net (code "98") (name "unconnected-(OK9A-A-Pad1)") (class "Default")
      (node (ref "OK9") (pin "1") (pinfunction "A_1") (pintype "passive"))
    )
    (net (code "99") (name "unconnected-(OK9A-C-Pad2)") (class "Default")
      (node (ref "OK9") (pin "2") (pinfunction "C_2") (pintype "passive"))
    )
    (net (code "100") (name "unconnected-(OK9A-COL-Pad8)") (class "Default")
      (node (ref "OK9") (pin "8") (pinfunction "COL_8") (pintype "passive"))
    )
    (net (code "101") (name "unconnected-(OK9A-EMIT-Pad7)") (class "Default")
      (node (ref "OK9") (pin "7") (pinfunction "EMIT_7") (pintype "passive"))
    )
    (net (code "102") (name "unconnected-(OK9B-A-Pad3)") (class "Default")
      (node (ref "OK9") (pin "3") (pinfunction "A_3") (pintype "passive"))
    )
    (net (code "103") (name "unconnected-(OK9B-C-Pad4)") (class "Default")
      (node (ref "OK9") (pin "4") (pinfunction "C_4") (pintype "passive"))
    )
    (net (code "104") (name "unconnected-(OK9B-COL-Pad6)") (class "Default")
      (node (ref "OK9") (pin "6") (pinfunction "COL_6") (pintype "passive"))
    )
    (net (code "105") (name "unconnected-(OK9B-EMIT-Pad5)") (class "Default")
      (node (ref "OK9") (pin "5") (pinfunction "EMIT_5") (pintype "passive"))
    )
    (net (code "106") (name "unconnected-(RN1B-1-Pad2)") (class "Default")
      (node (ref "RN1") (pin "2") (pinfunction "1_2") (pintype "passive"))
    )
    (net (code "107") (name "unconnected-(RN1C-1-Pad3)") (class "Default")
      (node (ref "RN1") (pin "3") (pinfunction "1_3") (pintype "passive"))
    )
    (net (code "108") (name "unconnected-(RN1F-1-Pad6)") (class "Default")
      (node (ref "RN1") (pin "6") (pinfunction "1_6") (pintype "passive"))
    )
    (net (code "109") (name "unconnected-(RN1G-1-Pad7)") (class "Default")
      (node (ref "RN1") (pin "7") (pinfunction "1_7") (pintype "passive"))
    )
    (net (code "110") (name "unconnected-(RN2-Pad1)") (class "Default")
      (node (ref "RN2") (pin "1") (pinfunction "1_1") (pintype "passive"))
    )
    (net (code "111") (name "unconnected-(RN2A-2-Pad16)") (class "Default")
      (node (ref "RN2") (pin "16") (pinfunction "2_16") (pintype "passive"))
    )
    (net (code "112") (name "unconnected-(RN2B-1-Pad2)") (class "Default")
      (node (ref "RN2") (pin "2") (pinfunction "1_2") (pintype "passive"))
    )
    (net (code "113") (name "unconnected-(RN2B-2-Pad15)") (class "Default")
      (node (ref "RN2") (pin "15") (pinfunction "2_15") (pintype "passive"))
    )
    (net (code "114") (name "unconnected-(RN2C-1-Pad3)") (class "Default")
      (node (ref "RN2") (pin "3") (pinfunction "1_3") (pintype "passive"))
    )
    (net (code "115") (name "unconnected-(RN2C-2-Pad14)") (class "Default")
      (node (ref "RN2") (pin "14") (pinfunction "2_14") (pintype "passive"))
    )
    (net (code "116") (name "unconnected-(RN2D-1-Pad4)") (class "Default")
      (node (ref "RN2") (pin "4") (pinfunction "1_4") (pintype "passive"))
    )
    (net (code "117") (name "unconnected-(RN2D-2-Pad13)") (class "Default")
      (node (ref "RN2") (pin "13") (pinfunction "2_13") (pintype "passive"))
    )
    (net (code "118") (name "unconnected-(RN2E-1-Pad5)") (class "Default")
      (node (ref "RN2") (pin "5") (pinfunction "1_5") (pintype "passive"))
    )
    (net (code "119") (name "unconnected-(RN2E-2-Pad12)") (class "Default")
      (node (ref "RN2") (pin "12") (pinfunction "2_12") (pintype "passive"))
    )
    (net (code "120") (name "unconnected-(RN2F-1-Pad6)") (class "Default")
      (node (ref "RN2") (pin "6") (pinfunction "1_6") (pintype "passive"))
    )
    (net (code "121") (name "unconnected-(RN2F-2-Pad11)") (class "Default")
      (node (ref "RN2") (pin "11") (pinfunction "2_11") (pintype "passive"))
    )
    (net (code "122") (name "unconnected-(RN2G-1-Pad7)") (class "Default")
      (node (ref "RN2") (pin "7") (pinfunction "1_7") (pintype "passive"))
    )
    (net (code "123") (name "unconnected-(RN2G-2-Pad10)") (class "Default")
      (node (ref "RN2") (pin "10") (pinfunction "2_10") (pintype "passive"))
    )
    (net (code "124") (name "unconnected-(RN2H-1-Pad8)") (class "Default")
      (node (ref "RN2") (pin "8") (pinfunction "1_8") (pintype "passive"))
    )
    (net (code "125") (name "unconnected-(RN2H-2-Pad9)") (class "Default")
      (node (ref "RN2") (pin "9") (pinfunction "2_9") (pintype "passive"))
    )
    (net (code "126") (name "unconnected-(U$1-Pad3V3)") (class "Default")
      (node (ref "U$1") (pin "3V3") (pinfunction "3V3_3V3") (pintype "bidirectional"))
    )
    (net (code "127") (name "unconnected-(U$1-PadAREF)") (class "Default")
      (node (ref "U$1") (pin "AREF") (pinfunction "AREF_AREF") (pintype "bidirectional"))
    )
    (net (code "128") (name "unconnected-(U$1-PadD0{slash}RX)") (class "Default")
      (node (ref "U$1") (pin "D0/RX") (pinfunction "D0/RX_D0/RX") (pintype "bidirectional"))
    )
    (net (code "129") (name "unconnected-(U$1-PadD1{slash}TX)") (class "Default")
      (node (ref "U$1") (pin "D1/TX") (pinfunction "D1/TX_D1/TX") (pintype "bidirectional"))
    )
    (net (code "130") (name "unconnected-(U$1-PadD2)") (class "Default")
      (node (ref "U$1") (pin "D2") (pinfunction "D2_D2") (pintype "bidirectional"))
    )
    (net (code "131") (name "unconnected-(U$1-PadD3)") (class "Default")
      (node (ref "U$1") (pin "D3") (pinfunction "D3_D3") (pintype "bidirectional"))
    )
    (net (code "132") (name "unconnected-(U$1-PadD4)") (class "Default")
      (node (ref "U$1") (pin "D4") (pinfunction "D4_D4") (pintype "bidirectional"))
    )
    (net (code "133") (name "unconnected-(U$1-PadD5)") (class "Default")
      (node (ref "U$1") (pin "D5") (pinfunction "D5_D5") (pintype "bidirectional"))
    )
    (net (code "134") (name "unconnected-(U$1-PadD6)") (class "Default")
      (node (ref "U$1") (pin "D6") (pinfunction "D6_D6") (pintype "bidirectional"))
    )
    (net (code "135") (name "unconnected-(U$1-PadD7)") (class "Default")
      (node (ref "U$1") (pin "D7") (pinfunction "D7_D7") (pintype "bidirectional"))
    )
    (net (code "136") (name "unconnected-(U$1-PadD8)") (class "Default")
      (node (ref "U$1") (pin "D8") (pinfunction "D8_D8") (pintype "bidirectional"))
    )
    (net (code "137") (name "unconnected-(U$1-PadD9)") (class "Default")
      (node (ref "U$1") (pin "D9") (pinfunction "D9_D9") (pintype "bidirectional"))
    )
    (net (code "138") (name "unconnected-(U$1-PadD10)") (class "Default")
      (node (ref "U$1") (pin "D10") (pinfunction "D10_D10") (pintype "bidirectional"))
    )
    (net (code "139") (name "unconnected-(U$1-PadD11)") (class "Default")
      (node (ref "U$1") (pin "D11") (pinfunction "D11_D11") (pintype "bidirectional"))
    )
    (net (code "140") (name "unconnected-(U$1-PadD12)") (class "Default")
      (node (ref "U$1") (pin "D12") (pinfunction "D12_D12") (pintype "bidirectional"))
    )
    (net (code "141") (name "unconnected-(U$1-PadD13)") (class "Default")
      (node (ref "U$1") (pin "D13") (pinfunction "D13_D13") (pintype "bidirectional"))
    )
    (net (code "142") (name "unconnected-(U$1-PadGND1)") (class "Default")
      (node (ref "U$1") (pin "GND1") (pinfunction "GND1_GND1") (pintype "bidirectional"))
    )
    (net (code "143") (name "unconnected-(U$1-PadRESET)") (class "Default")
      (node (ref "U$1") (pin "RESET") (pinfunction "RESET_RESET") (pintype "bidirectional"))
    )
    (net (code "144") (name "unconnected-(U$1-PadRESET1)") (class "Default")
      (node (ref "U$1") (pin "RESET1") (pinfunction "RESET1_RESET1") (pintype "bidirectional"))
    )
    (net (code "145") (name "unconnected-(U$1-PadVIN)") (class "Default")
      (node (ref "U$1") (pin "VIN") (pinfunction "VIN_VIN") (pintype "bidirectional"))
    )
    (net (code "146") (name "unconnected-(X2-Pad1)") (class "Default")
      (node (ref "X2") (pin "1") (pinfunction "1_1") (pintype "passive"))
    )
    (net (code "147") (name "unconnected-(X2B-1-Pad2)") (class "Default")
      (node (ref "X2") (pin "2") (pinfunction "1_2") (pintype "passive"))
    )
    (net (code "148") (name "unconnected-(X2C-1-Pad3)") (class "Default")
      (node (ref "X2") (pin "3") (pinfunction "1_3") (pintype "passive"))
    )
    (net (code "149") (name "unconnected-(X2D-1-Pad4)") (class "Default")
      (node (ref "X2") (pin "4") (pinfunction "1_4") (pintype "passive"))
    )
    (net (code "150") (name "unconnected-(X5B-1-Pad2)") (class "Default")
      (node (ref "X5") (pin "2") (pinfunction "1_2") (pintype "passive"))
    )
    (net (code "151") (name "unconnected-(X5D-1-Pad4)") (class "Default")
      (node (ref "X5") (pin "4") (pinfunction "1_4") (pintype "passive"))
    )
    (net (code "152") (name "unconnected-(X6B-1-Pad2)") (class "Default")
      (node (ref "X6") (pin "2") (pinfunction "1_2") (pintype "passive"))
    )
    (net (code "153") (name "unconnected-(X6D-1-Pad4)") (class "Default")
      (node (ref "X6") (pin "4") (pinfunction "1_4") (pintype "passive"))
    )
    (net (code "154") (name "unconnected-(X7B-1-Pad2)") (class "Default")
      (node (ref "X7") (pin "2") (pinfunction "1_2") (pintype "passive"))
    )
    (net (code "155") (name "unconnected-(X7D-1-Pad4)") (class "Default")
      (node (ref "X7") (pin "4") (pinfunction "1_4") (pintype "passive"))
    )
    (net (code "156") (name "unconnected-(X8B-1-Pad2)") (class "Default")
      (node (ref "X8") (pin "2") (pinfunction "1_2") (pintype "passive"))
    )
    (net (code "157") (name "unconnected-(X8D-1-Pad4)") (class "Default")
      (node (ref "X8") (pin "4") (pinfunction "1_4") (pintype "passive"))
    )
    (net (code "158") (name "unconnected-(XR1A-A-Pad1)") (class "Default")
      (node (ref "XR1") (pin "1") (pinfunction "A_1") (pintype "passive"))
    )
    (net (code "159") (name "unconnected-(XR1A-EMI-Pad10)") (class "Default")
      (node (ref "XR1") (pin "10") (pinfunction "EMI_10") (pintype "passive"))
    )
    (net (code "160") (name "unconnected-(XR1B-A-Pad2)") (class "Default")
      (node (ref "XR1") (pin "2") (pinfunction "A_2") (pintype "passive"))
    )
    (net (code "161") (name "unconnected-(XR1B-EMI-Pad9)") (class "Default")
      (node (ref "XR1") (pin "9") (pinfunction "EMI_9") (pintype "passive"))
    )
    (net (code "162") (name "unconnected-(XR1C-A-Pad4)") (class "Default")
      (node (ref "XR1") (pin "4") (pinfunction "A_4") (pintype "passive"))
    )
    (net (code "163") (name "unconnected-(XR1C-EMI-Pad7)") (class "Default")
      (node (ref "XR1") (pin "7") (pinfunction "EMI_7") (pintype "passive"))
    )
    (net (code "164") (name "unconnected-(XR1D-A-Pad5)") (class "Default")
      (node (ref "XR1") (pin "5") (pinfunction "A_5") (pintype "passive"))
    )
    (net (code "165") (name "unconnected-(XR1D-EMI-Pad6)") (class "Default")
      (node (ref "XR1") (pin "6") (pinfunction "EMI_6") (pintype "passive"))
    )
    (net (code "166") (name "unconnected-(XR1E-COM-CAT-Pad3)") (class "Default")
      (node (ref "XR1") (pin "3") (pinfunction "COM-CAT_3") (pintype "passive"))
    )
    (net (code "167") (name "unconnected-(XR1E-COM-COL-Pad8)") (class "Default")
      (node (ref "XR1") (pin "8") (pinfunction "COM-COL_8") (pintype "passive"))
    )
  )
)
